# village_control.net
KiCad netlist of a schematic drawn in EAGLE
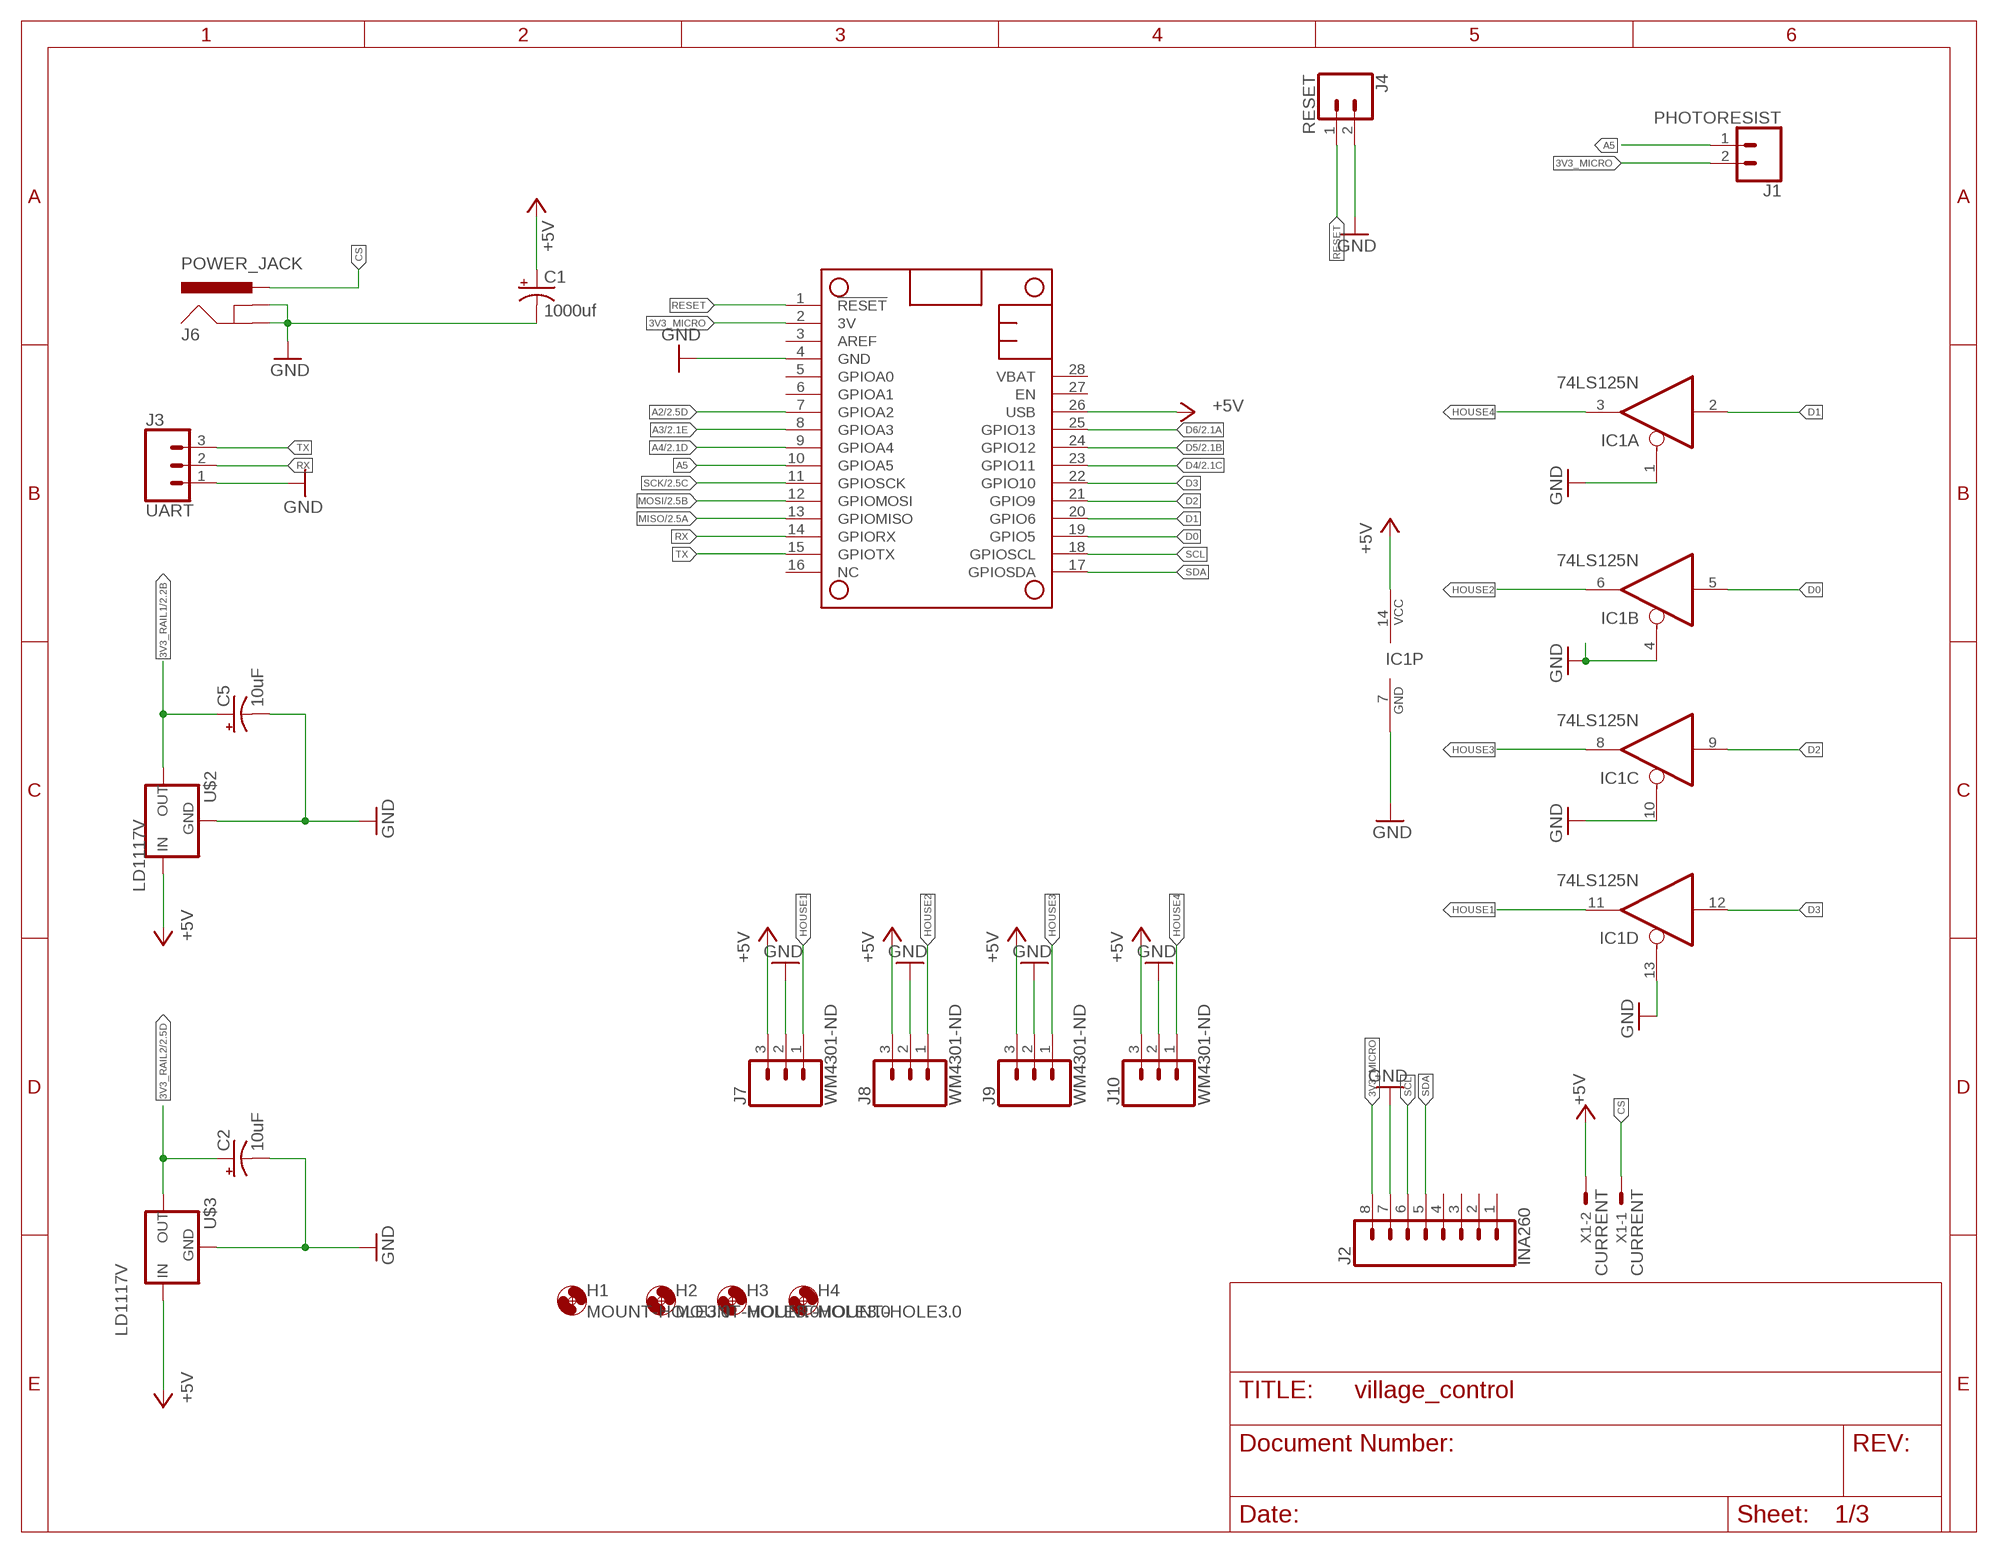
[diagram p0: schematic, sheet 1]
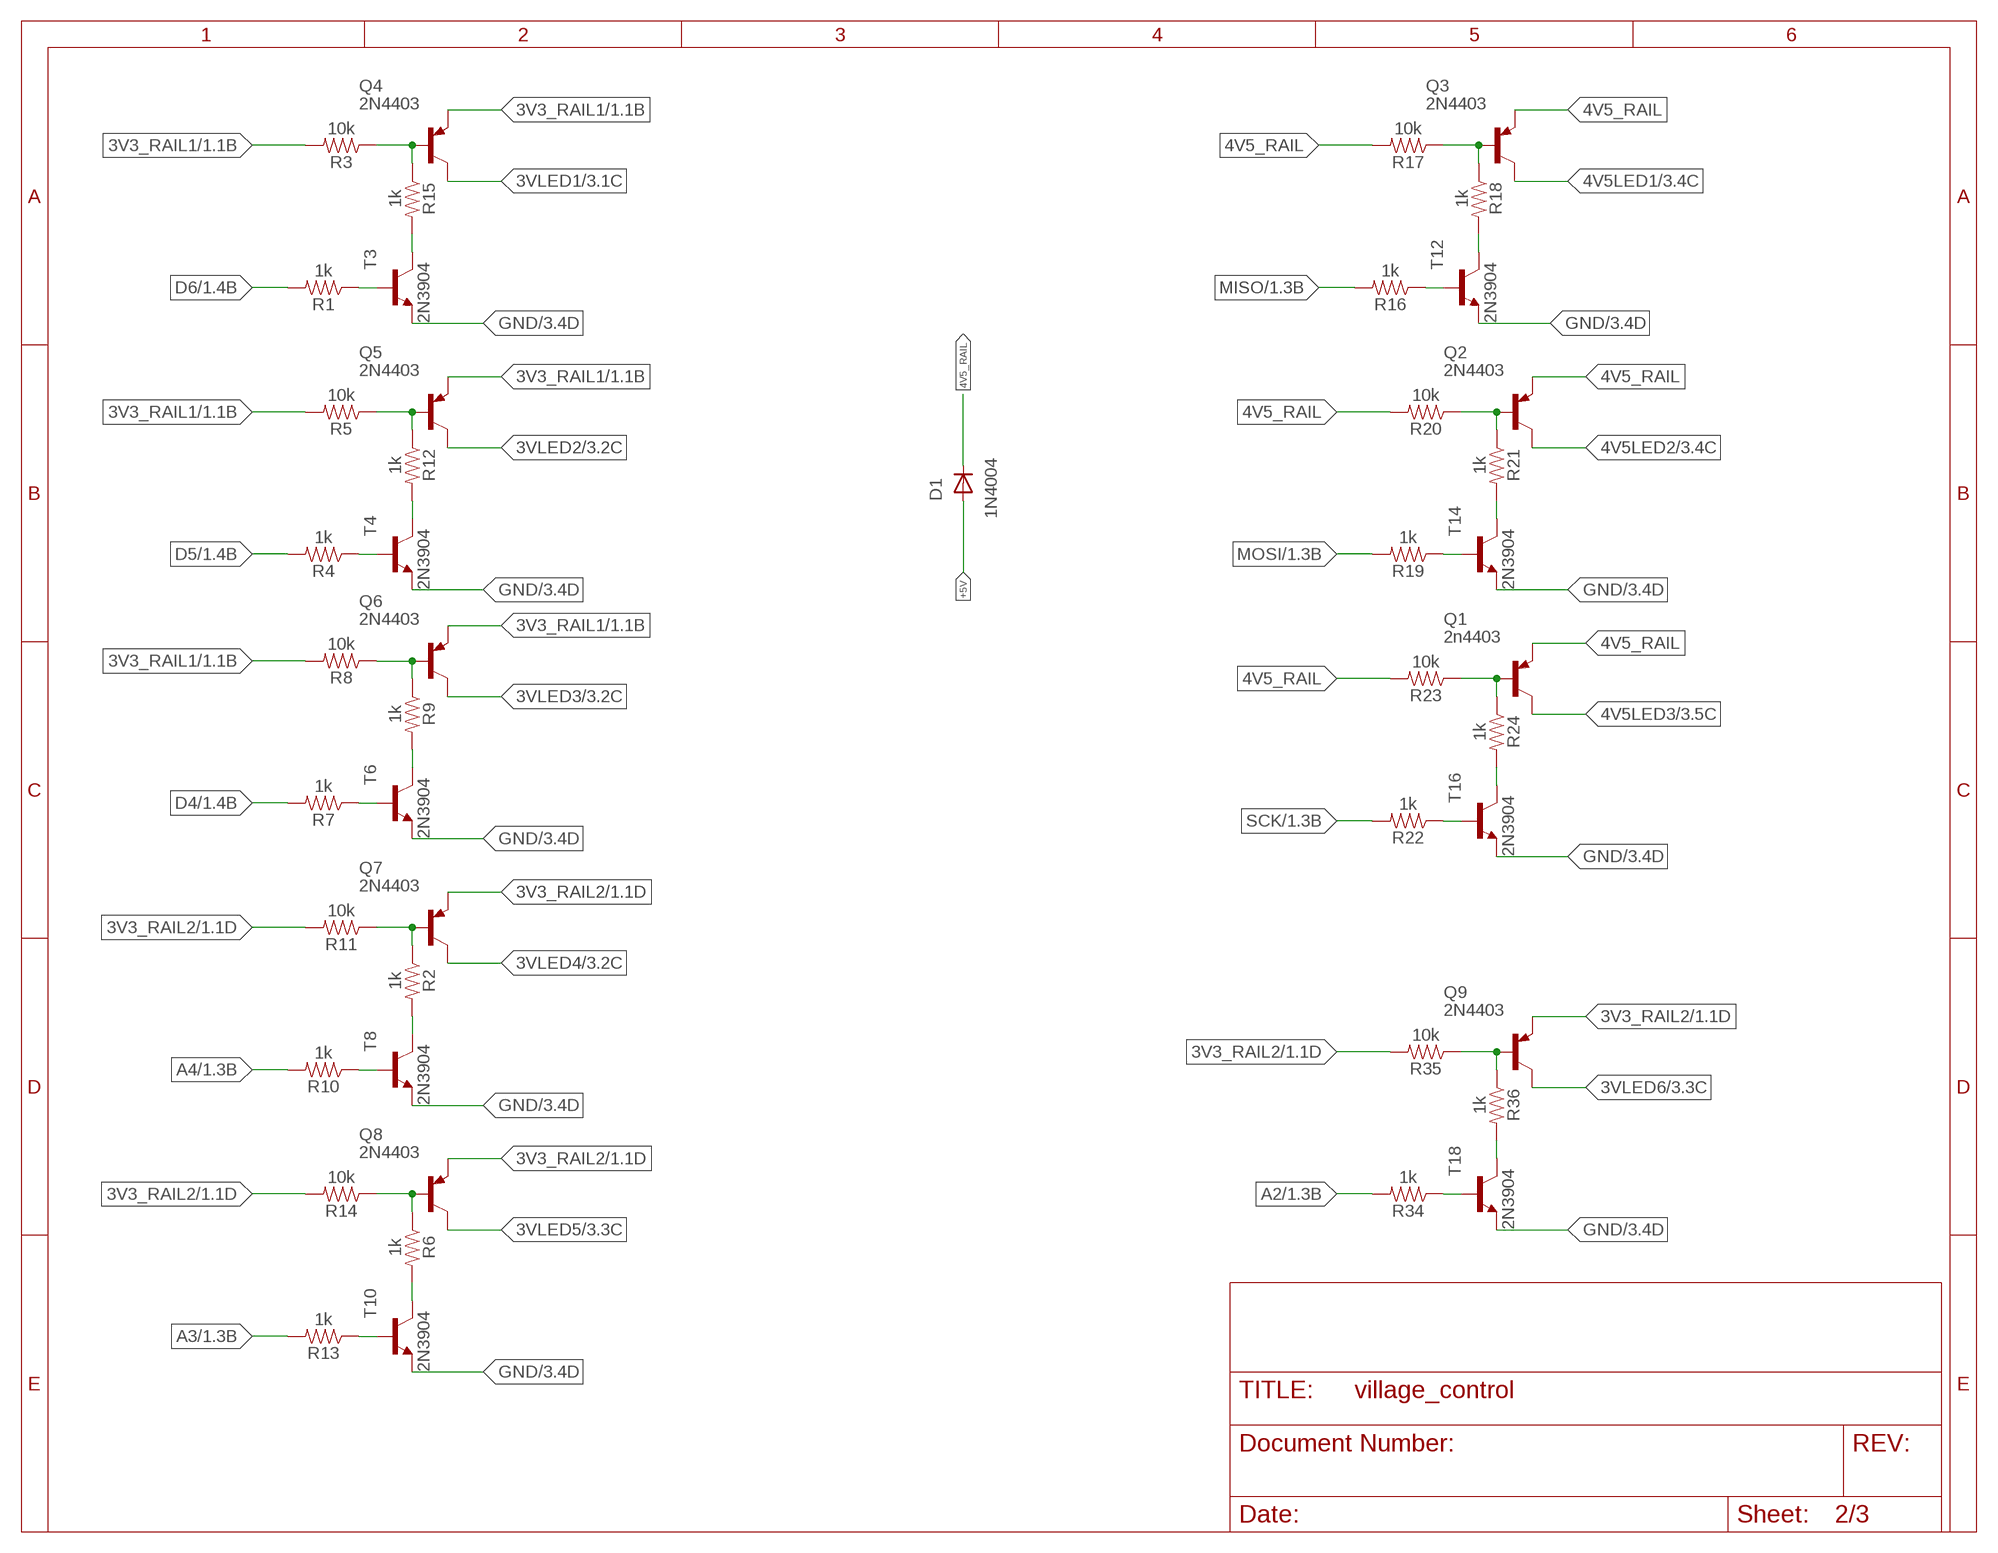
[diagram p1: schematic, sheet 2]
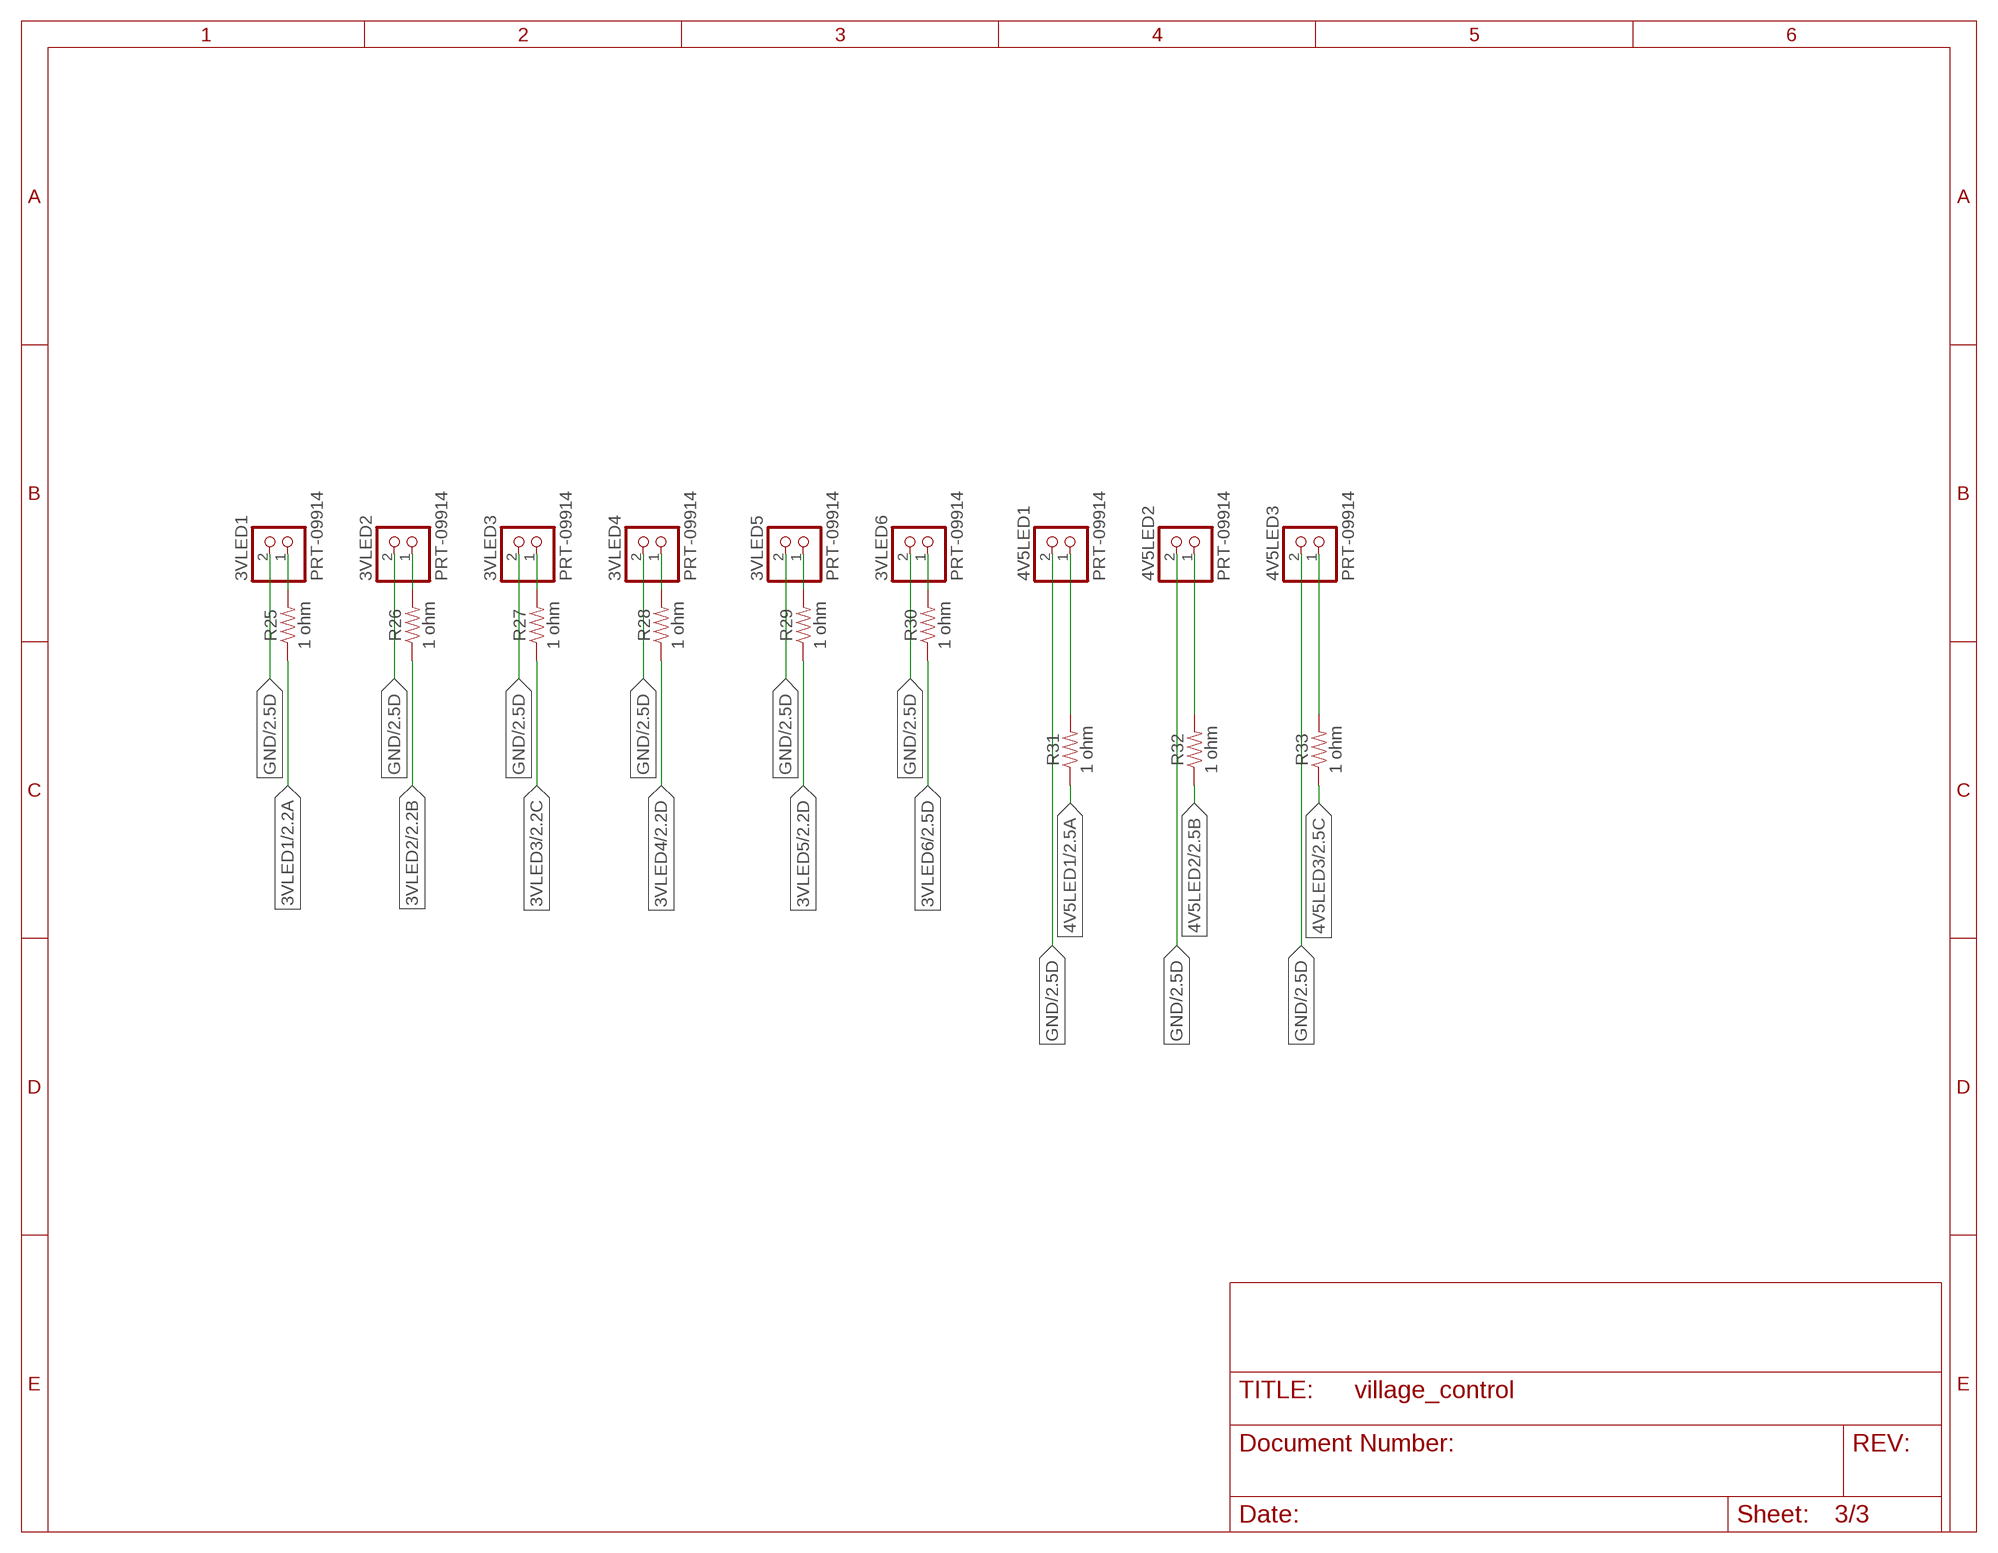
[diagram p2: schematic, sheet 3]

(export (version "E")
  (design (tool "Eeschema 10.0.6"))
  (components
    (comp (ref "D1")
      (value "1N4004")
      (footprint "eagle-import:DO41-10")
      (libsource (lib "eagle-import") (part "1N4004"))
    )
    (comp (ref "Q1")
      (value "2n4403")
      (footprint "eagle-import:TO92")
      (libsource (lib "eagle-import") (part "2N3906"))
    )
    (comp (ref "Q2")
      (value "2N4403")
      (footprint "eagle-import:TO92")
      (libsource (lib "eagle-import") (part "2N3906"))
    )
    (comp (ref "Q3")
      (value "2N4403")
      (footprint "eagle-import:TO92")
      (libsource (lib "eagle-import") (part "2N3906"))
    )
    (comp (ref "Q4")
      (value "2N4403")
      (footprint "eagle-import:TO92")
      (libsource (lib "eagle-import") (part "2N3906"))
    )
    (comp (ref "Q5")
      (value "2N4403")
      (footprint "eagle-import:TO92")
      (libsource (lib "eagle-import") (part "2N3906"))
    )
    (comp (ref "Q6")
      (value "2N4403")
      (footprint "eagle-import:TO92")
      (libsource (lib "eagle-import") (part "2N3906"))
    )
    (comp (ref "Q7")
      (value "2N4403")
      (footprint "eagle-import:TO92")
      (libsource (lib "eagle-import") (part "2N3906"))
    )
    (comp (ref "Q8")
      (value "2N4403")
      (footprint "eagle-import:TO92")
      (libsource (lib "eagle-import") (part "2N3906"))
    )
    (comp (ref "Q9")
      (value "2N4403")
      (footprint "eagle-import:TO92")
      (libsource (lib "eagle-import") (part "2N3906"))
    )
    (comp (ref "R1")
      (value "1k")
      (footprint "eagle-import:AXIAL-0.3")
      (libsource (lib "eagle-import") (part "1KOHM-HORIZ-1/4W-1%"))
    )
    (comp (ref "R2")
      (value "1k")
      (footprint "eagle-import:AXIAL-0.3")
      (libsource (lib "eagle-import") (part "1KOHM-HORIZ-1/4W-1%"))
    )
    (comp (ref "R3")
      (value "10k")
      (footprint "eagle-import:AXIAL-0.3")
      (libsource (lib "eagle-import") (part "1KOHM-HORIZ-1/4W-5%"))
    )
    (comp (ref "R4")
      (value "1k")
      (footprint "eagle-import:AXIAL-0.3")
      (libsource (lib "eagle-import") (part "1KOHM-HORIZ-1/4W-1%"))
    )
    (comp (ref "R5")
      (value "10k")
      (footprint "eagle-import:AXIAL-0.3")
      (libsource (lib "eagle-import") (part "1KOHM-HORIZ-1/4W-5%"))
    )
    (comp (ref "R6")
      (value "1k")
      (footprint "eagle-import:AXIAL-0.3")
      (libsource (lib "eagle-import") (part "1KOHM-HORIZ-1/4W-1%"))
    )
    (comp (ref "R7")
      (value "1k")
      (footprint "eagle-import:AXIAL-0.3")
      (libsource (lib "eagle-import") (part "1KOHM-HORIZ-1/4W-1%"))
    )
    (comp (ref "R8")
      (value "10k")
      (footprint "eagle-import:AXIAL-0.3")
      (libsource (lib "eagle-import") (part "1KOHM-HORIZ-1/4W-5%"))
    )
    (comp (ref "R9")
      (value "1k")
      (footprint "eagle-import:AXIAL-0.3")
      (libsource (lib "eagle-import") (part "1KOHM-HORIZ-1/4W-1%"))
    )
    (comp (ref "R10")
      (value "1k")
      (footprint "eagle-import:AXIAL-0.3")
      (libsource (lib "eagle-import") (part "1KOHM-HORIZ-1/4W-1%"))
    )
    (comp (ref "R11")
      (value "10k")
      (footprint "eagle-import:AXIAL-0.3")
      (libsource (lib "eagle-import") (part "1KOHM-HORIZ-1/4W-5%"))
    )
    (comp (ref "R12")
      (value "1k")
      (footprint "eagle-import:AXIAL-0.3")
      (libsource (lib "eagle-import") (part "1KOHM-HORIZ-1/4W-1%"))
    )
    (comp (ref "R13")
      (value "1k")
      (footprint "eagle-import:AXIAL-0.3")
      (libsource (lib "eagle-import") (part "1KOHM-HORIZ-1/4W-1%"))
    )
    (comp (ref "R14")
      (value "10k")
      (footprint "eagle-import:AXIAL-0.3")
      (libsource (lib "eagle-import") (part "1KOHM-HORIZ-1/4W-5%"))
    )
    (comp (ref "R15")
      (value "1k")
      (footprint "eagle-import:AXIAL-0.3")
      (libsource (lib "eagle-import") (part "1KOHM-HORIZ-1/4W-1%"))
    )
    (comp (ref "R16")
      (value "1k")
      (footprint "eagle-import:AXIAL-0.3")
      (libsource (lib "eagle-import") (part "1KOHM-HORIZ-1/4W-1%"))
    )
    (comp (ref "R17")
      (value "10k")
      (footprint "eagle-import:AXIAL-0.3")
      (libsource (lib "eagle-import") (part "1KOHM-HORIZ-1/4W-5%"))
    )
    (comp (ref "R18")
      (value "1k")
      (footprint "eagle-import:AXIAL-0.3")
      (libsource (lib "eagle-import") (part "1KOHM-HORIZ-1/4W-1%"))
    )
    (comp (ref "R19")
      (value "1k")
      (footprint "eagle-import:AXIAL-0.3")
      (libsource (lib "eagle-import") (part "1KOHM-HORIZ-1/4W-1%"))
    )
    (comp (ref "R20")
      (value "10k")
      (footprint "eagle-import:AXIAL-0.3")
      (libsource (lib "eagle-import") (part "1KOHM-HORIZ-1/4W-5%"))
    )
    (comp (ref "R21")
      (value "1k")
      (footprint "eagle-import:AXIAL-0.3")
      (libsource (lib "eagle-import") (part "1KOHM-HORIZ-1/4W-1%"))
    )
    (comp (ref "R22")
      (value "1k")
      (footprint "eagle-import:AXIAL-0.3")
      (libsource (lib "eagle-import") (part "1KOHM-HORIZ-1/4W-1%"))
    )
    (comp (ref "R23")
      (value "10k")
      (footprint "eagle-import:AXIAL-0.3")
      (libsource (lib "eagle-import") (part "1KOHM-HORIZ-1/4W-5%"))
    )
    (comp (ref "R24")
      (value "1k")
      (footprint "eagle-import:AXIAL-0.3")
      (libsource (lib "eagle-import") (part "1KOHM-HORIZ-1/4W-1%"))
    )
    (comp (ref "R34")
      (value "1k")
      (footprint "eagle-import:AXIAL-0.3")
      (libsource (lib "eagle-import") (part "1KOHM-HORIZ-1/4W-1%"))
    )
    (comp (ref "R35")
      (value "10k")
      (footprint "eagle-import:AXIAL-0.3")
      (libsource (lib "eagle-import") (part "1KOHM-HORIZ-1/4W-5%"))
    )
    (comp (ref "R36")
      (value "1k")
      (footprint "eagle-import:AXIAL-0.3")
      (libsource (lib "eagle-import") (part "1KOHM-HORIZ-1/4W-1%"))
    )
    (comp (ref "T3")
      (value "2N3904")
      (footprint "eagle-import:TO92")
      (libsource (lib "eagle-import") (part "2N3904"))
    )
    (comp (ref "T4")
      (value "2N3904")
      (footprint "eagle-import:TO92")
      (libsource (lib "eagle-import") (part "2N3904"))
    )
    (comp (ref "T6")
      (value "2N3904")
      (footprint "eagle-import:TO92")
      (libsource (lib "eagle-import") (part "2N3904"))
    )
    (comp (ref "T8")
      (value "2N3904")
      (footprint "eagle-import:TO92")
      (libsource (lib "eagle-import") (part "2N3904"))
    )
    (comp (ref "T10")
      (value "2N3904")
      (footprint "eagle-import:TO92")
      (libsource (lib "eagle-import") (part "2N3904"))
    )
    (comp (ref "T12")
      (value "2N3904")
      (footprint "eagle-import:TO92")
      (libsource (lib "eagle-import") (part "2N3904"))
    )
    (comp (ref "T14")
      (value "2N3904")
      (footprint "eagle-import:TO92")
      (libsource (lib "eagle-import") (part "2N3904"))
    )
    (comp (ref "T16")
      (value "2N3904")
      (footprint "eagle-import:TO92")
      (libsource (lib "eagle-import") (part "2N3904"))
    )
    (comp (ref "T18")
      (value "2N3904")
      (footprint "eagle-import:TO92")
      (libsource (lib "eagle-import") (part "2N3904"))
    )
    (comp (ref "3VLED1")
      (value "PRT-09914")
      (footprint "eagle-import:JST-PH-2-THM")
      (libsource (lib "eagle-import") (part "JST_2PIN-THM"))
    )
    (comp (ref "3VLED2")
      (value "PRT-09914")
      (footprint "eagle-import:JST-PH-2-THM")
      (libsource (lib "eagle-import") (part "JST_2PIN-THM"))
    )
    (comp (ref "3VLED3")
      (value "PRT-09914")
      (footprint "eagle-import:JST-PH-2-THM")
      (libsource (lib "eagle-import") (part "JST_2PIN-THM"))
    )
    (comp (ref "3VLED4")
      (value "PRT-09914")
      (footprint "eagle-import:JST-PH-2-THM")
      (libsource (lib "eagle-import") (part "JST_2PIN-THM"))
    )
    (comp (ref "3VLED5")
      (value "PRT-09914")
      (footprint "eagle-import:JST-PH-2-THM")
      (libsource (lib "eagle-import") (part "JST_2PIN-THM"))
    )
    (comp (ref "3VLED6")
      (value "PRT-09914")
      (footprint "eagle-import:JST-PH-2-THM")
      (libsource (lib "eagle-import") (part "JST_2PIN-THM"))
    )
    (comp (ref "4V5LED1")
      (value "PRT-09914")
      (footprint "eagle-import:JST-PH-2-THM")
      (libsource (lib "eagle-import") (part "JST_2PIN-THM"))
    )
    (comp (ref "4V5LED2")
      (value "PRT-09914")
      (footprint "eagle-import:JST-PH-2-THM")
      (libsource (lib "eagle-import") (part "JST_2PIN-THM"))
    )
    (comp (ref "4V5LED3")
      (value "PRT-09914")
      (footprint "eagle-import:JST-PH-2-THM")
      (libsource (lib "eagle-import") (part "JST_2PIN-THM"))
    )
    (comp (ref "R25")
      (value "1 ohm")
      (footprint "eagle-import:AXIAL-0.3")
      (libsource (lib "eagle-import") (part "1KOHM-HORIZ-1/4W-5%"))
    )
    (comp (ref "R26")
      (value "1 ohm")
      (footprint "eagle-import:AXIAL-0.3")
      (libsource (lib "eagle-import") (part "1KOHM-HORIZ-1/4W-5%"))
    )
    (comp (ref "R27")
      (value "1 ohm")
      (footprint "eagle-import:AXIAL-0.3")
      (libsource (lib "eagle-import") (part "1KOHM-HORIZ-1/4W-5%"))
    )
    (comp (ref "R28")
      (value "1 ohm")
      (footprint "eagle-import:AXIAL-0.3")
      (libsource (lib "eagle-import") (part "1KOHM-HORIZ-1/4W-5%"))
    )
    (comp (ref "R29")
      (value "1 ohm")
      (footprint "eagle-import:AXIAL-0.3")
      (libsource (lib "eagle-import") (part "1KOHM-HORIZ-1/4W-5%"))
    )
    (comp (ref "R30")
      (value "1 ohm")
      (footprint "eagle-import:AXIAL-0.3")
      (libsource (lib "eagle-import") (part "1KOHM-HORIZ-1/4W-5%"))
    )
    (comp (ref "R31")
      (value "1 ohm")
      (footprint "eagle-import:AXIAL-0.3")
      (libsource (lib "eagle-import") (part "1KOHM-HORIZ-1/4W-5%"))
    )
    (comp (ref "R32")
      (value "1 ohm")
      (footprint "eagle-import:AXIAL-0.3")
      (libsource (lib "eagle-import") (part "1KOHM-HORIZ-1/4W-5%"))
    )
    (comp (ref "R33")
      (value "1 ohm")
      (footprint "eagle-import:AXIAL-0.3")
      (libsource (lib "eagle-import") (part "1KOHM-HORIZ-1/4W-5%"))
    )
    (comp (ref "C1")
      (value "1000uf")
      (footprint "eagle-import:CPOL-RADIAL-5MM-10MM")
      (libsource (lib "eagle-import") (part "1000UF-RADIAL-5MM-25V-20%"))
    )
    (comp (ref "C2")
      (value "10uF")
      (footprint "eagle-import:CPOL-RADIAL-2.5MM-5MM-KIT")
      (libsource (lib "eagle-import") (part "10UF-POLAR-RADIAL-2.5MM-KIT-25V-20%"))
    )
    (comp (ref "C5")
      (value "10uF")
      (footprint "eagle-import:CPOL-RADIAL-2.5MM-5MM-KIT")
      (libsource (lib "eagle-import") (part "10UF-POLAR-RADIAL-2.5MM-KIT-25V-20%"))
    )
    (comp (ref "H1")
      (value "MOUNT-HOLE3.0")
      (footprint "eagle-import:3,0")
      (libsource (lib "eagle-import") (part "MOUNT-HOLE3.0"))
    )
    (comp (ref "H2")
      (value "MOUNT-HOLE3.0")
      (footprint "eagle-import:3,0")
      (libsource (lib "eagle-import") (part "MOUNT-HOLE3.0"))
    )
    (comp (ref "H3")
      (value "MOUNT-HOLE3.0")
      (footprint "eagle-import:3,0")
      (libsource (lib "eagle-import") (part "MOUNT-HOLE3.0"))
    )
    (comp (ref "H4")
      (value "MOUNT-HOLE3.0")
      (footprint "eagle-import:3,0")
      (libsource (lib "eagle-import") (part "MOUNT-HOLE3.0"))
    )
    (comp (ref "IC1")
      (value "74LS125N")
      (footprint "eagle-import:DIL14")
      (libsource (lib "eagle-import") (part "74125NLS"))
    )
    (comp (ref "J1")
      (value "PHOTORESIST")
      (footprint "eagle-import:1X02")
      (libsource (lib "eagle-import") (part "CONN_02"))
    )
    (comp (ref "J2")
      (value "INA260")
      (footprint "eagle-import:1X08")
      (libsource (lib "eagle-import") (part "CONN_08{dblquote}"))
    )
    (comp (ref "J3")
      (value "UART")
      (footprint "eagle-import:1X03")
      (libsource (lib "eagle-import") (part "CONN_03"))
    )
    (comp (ref "J4")
      (value "RESET")
      (footprint "eagle-import:1X02")
      (libsource (lib "eagle-import") (part "CONN_02"))
    )
    (comp (ref "J6")
      (value "POWER_JACK")
      (footprint "eagle-import:POWER_JACK_PTH")
      (libsource (lib "eagle-import") (part "POWER_JACK"))
    )
    (comp (ref "J7")
      (value "WM4301-ND")
      (footprint "eagle-import:1X03")
      (libsource (lib "eagle-import") (part "CONN_03"))
    )
    (comp (ref "J8")
      (value "WM4301-ND")
      (footprint "eagle-import:1X03")
      (libsource (lib "eagle-import") (part "CONN_03"))
    )
    (comp (ref "J9")
      (value "WM4301-ND")
      (footprint "eagle-import:1X03")
      (libsource (lib "eagle-import") (part "CONN_03"))
    )
    (comp (ref "J10")
      (value "WM4301-ND")
      (footprint "eagle-import:1X03")
      (libsource (lib "eagle-import") (part "CONN_03"))
    )
    (comp (ref "MS2")
      (value "FEATHERWING_NODIM")
      (footprint "eagle-import:FEATHERWING_DIM")
      (libsource (lib "eagle-import") (part "FEATHERWING_NODIM"))
    )
    (comp (ref "U$2")
      (value "LD1117V")
      (footprint "eagle-import:78XXL")
      (libsource (lib "eagle-import") (part "V_REG_LD1117VXX"))
    )
    (comp (ref "U$3")
      (value "LD1117V")
      (footprint "eagle-import:78XXL")
      (libsource (lib "eagle-import") (part "V_REG_LD1117VXX"))
    )
    (comp (ref "X1")
      (value "CURRENT")
      (footprint "eagle-import:KK-156-2")
      (fields (field (name "MF") "MOLEX"))
      (libsource (lib "eagle-import") (part "KK-156-2"))
    )
  )
  (nets
    (net (code "1") (name "+5V") (class "Default")
      (node (ref "C1") (pin "+") (pinfunction "+_+") (pintype "passive"))
      (node (ref "D1") (pin "A") (pinfunction "A_A") (pintype "passive"))
      (node (ref "IC1") (pin "14") (pinfunction "VCC_14") (pintype "power_in"))
      (node (ref "J10") (pin "3") (pinfunction "3_3") (pintype "passive"))
      (node (ref "J7") (pin "3") (pinfunction "3_3") (pintype "passive"))
      (node (ref "J8") (pin "3") (pinfunction "3_3") (pintype "passive"))
      (node (ref "J9") (pin "3") (pinfunction "3_3") (pintype "passive"))
      (node (ref "MS2") (pin "26") (pinfunction "USB_26") (pintype "power_in"))
      (node (ref "U$2") (pin "OUT") (pinfunction "IN_OUT") (pintype "input"))
      (node (ref "U$3") (pin "OUT") (pinfunction "IN_OUT") (pintype "input"))
      (node (ref "X1") (pin "2") (pinfunction "S_2") (pintype "passive"))
    )
    (net (code "2") (name "3V3_MICRO") (class "Default")
      (node (ref "J1") (pin "2") (pinfunction "2_2") (pintype "passive"))
      (node (ref "J2") (pin "8") (pinfunction "8_8") (pintype "passive"))
      (node (ref "MS2") (pin "2") (pinfunction "3V_2") (pintype "power_in"))
    )
    (net (code "3") (name "3V3_RAIL1") (class "Default")
      (node (ref "C5") (pin "1") (pinfunction "+_1") (pintype "passive"))
      (node (ref "Q4") (pin "3") (pinfunction "E_3") (pintype "passive"))
      (node (ref "Q5") (pin "3") (pinfunction "E_3") (pintype "passive"))
      (node (ref "Q6") (pin "3") (pinfunction "E_3") (pintype "passive"))
      (node (ref "R3") (pin "P$2") (pinfunction "2_P$2") (pintype "passive"))
      (node (ref "R5") (pin "P$2") (pinfunction "2_P$2") (pintype "passive"))
      (node (ref "R8") (pin "P$2") (pinfunction "2_P$2") (pintype "passive"))
      (node (ref "U$2") (pin "GND") (pinfunction "OUT_GND") (pintype "passive"))
    )
    (net (code "4") (name "3V3_RAIL2") (class "Default")
      (node (ref "C2") (pin "1") (pinfunction "+_1") (pintype "passive"))
      (node (ref "Q7") (pin "3") (pinfunction "E_3") (pintype "passive"))
      (node (ref "Q8") (pin "3") (pinfunction "E_3") (pintype "passive"))
      (node (ref "Q9") (pin "3") (pinfunction "E_3") (pintype "passive"))
      (node (ref "R11") (pin "P$2") (pinfunction "2_P$2") (pintype "passive"))
      (node (ref "R14") (pin "P$2") (pinfunction "2_P$2") (pintype "passive"))
      (node (ref "R35") (pin "P$2") (pinfunction "2_P$2") (pintype "passive"))
      (node (ref "U$3") (pin "GND") (pinfunction "OUT_GND") (pintype "passive"))
    )
    (net (code "5") (name "3VLED1") (class "Default")
      (node (ref "Q4") (pin "1") (pinfunction "C_1") (pintype "passive"))
      (node (ref "R25") (pin "P$1") (pinfunction "1_P$1") (pintype "passive"))
    )
    (net (code "6") (name "3VLED2") (class "Default")
      (node (ref "Q5") (pin "1") (pinfunction "C_1") (pintype "passive"))
      (node (ref "R26") (pin "P$1") (pinfunction "1_P$1") (pintype "passive"))
    )
    (net (code "7") (name "3VLED3") (class "Default")
      (node (ref "Q6") (pin "1") (pinfunction "C_1") (pintype "passive"))
      (node (ref "R27") (pin "P$1") (pinfunction "1_P$1") (pintype "passive"))
    )
    (net (code "8") (name "3VLED4") (class "Default")
      (node (ref "Q7") (pin "1") (pinfunction "C_1") (pintype "passive"))
      (node (ref "R28") (pin "P$1") (pinfunction "1_P$1") (pintype "passive"))
    )
    (net (code "9") (name "3VLED5") (class "Default")
      (node (ref "Q8") (pin "1") (pinfunction "C_1") (pintype "passive"))
      (node (ref "R29") (pin "P$1") (pinfunction "1_P$1") (pintype "passive"))
    )
    (net (code "10") (name "3VLED6") (class "Default")
      (node (ref "Q9") (pin "1") (pinfunction "C_1") (pintype "passive"))
      (node (ref "R30") (pin "P$1") (pinfunction "1_P$1") (pintype "passive"))
    )
    (net (code "11") (name "4V5LED1") (class "Default")
      (node (ref "Q3") (pin "1") (pinfunction "C_1") (pintype "passive"))
      (node (ref "R31") (pin "P$1") (pinfunction "1_P$1") (pintype "passive"))
    )
    (net (code "12") (name "4V5LED2") (class "Default")
      (node (ref "Q2") (pin "1") (pinfunction "C_1") (pintype "passive"))
      (node (ref "R32") (pin "P$1") (pinfunction "1_P$1") (pintype "passive"))
    )
    (net (code "13") (name "4V5LED3") (class "Default")
      (node (ref "Q1") (pin "1") (pinfunction "C_1") (pintype "passive"))
      (node (ref "R33") (pin "P$1") (pinfunction "1_P$1") (pintype "passive"))
    )
    (net (code "14") (name "4V5_RAIL") (class "Default")
      (node (ref "D1") (pin "C") (pinfunction "C_C") (pintype "passive"))
      (node (ref "Q1") (pin "3") (pinfunction "E_3") (pintype "passive"))
      (node (ref "Q2") (pin "3") (pinfunction "E_3") (pintype "passive"))
      (node (ref "Q3") (pin "3") (pinfunction "E_3") (pintype "passive"))
      (node (ref "R17") (pin "P$2") (pinfunction "2_P$2") (pintype "passive"))
      (node (ref "R20") (pin "P$2") (pinfunction "2_P$2") (pintype "passive"))
      (node (ref "R23") (pin "P$2") (pinfunction "2_P$2") (pintype "passive"))
    )
    (net (code "15") (name "A2") (class "Default")
      (node (ref "MS2") (pin "7") (pinfunction "GPIOA2_7") (pintype "bidirectional"))
      (node (ref "R34") (pin "P$2") (pinfunction "2_P$2") (pintype "passive"))
    )
    (net (code "16") (name "A3") (class "Default")
      (node (ref "MS2") (pin "8") (pinfunction "GPIOA3_8") (pintype "bidirectional"))
      (node (ref "R13") (pin "P$2") (pinfunction "2_P$2") (pintype "passive"))
    )
    (net (code "17") (name "A4") (class "Default")
      (node (ref "MS2") (pin "9") (pinfunction "GPIOA4_9") (pintype "bidirectional"))
      (node (ref "R10") (pin "P$2") (pinfunction "2_P$2") (pintype "passive"))
    )
    (net (code "18") (name "A5") (class "Default")
      (node (ref "J1") (pin "1") (pinfunction "1_1") (pintype "passive"))
      (node (ref "MS2") (pin "10") (pinfunction "GPIOA5_10") (pintype "bidirectional"))
    )
    (net (code "19") (name "CS") (class "Default")
      (node (ref "J6") (pin "PWR") (pinfunction "PWR_PWR") (pintype "bidirectional"))
      (node (ref "X1") (pin "1") (pinfunction "S_1") (pintype "passive"))
    )
    (net (code "20") (name "D0") (class "Default")
      (node (ref "IC1") (pin "5") (pinfunction "I_5") (pintype "input"))
      (node (ref "MS2") (pin "19") (pinfunction "GPIO5_19") (pintype "bidirectional"))
    )
    (net (code "21") (name "D1") (class "Default")
      (node (ref "IC1") (pin "2") (pinfunction "I_2") (pintype "input"))
      (node (ref "MS2") (pin "20") (pinfunction "GPIO6_20") (pintype "bidirectional"))
    )
    (net (code "22") (name "D2") (class "Default")
      (node (ref "IC1") (pin "9") (pinfunction "I_9") (pintype "input"))
      (node (ref "MS2") (pin "21") (pinfunction "GPIO9_21") (pintype "bidirectional"))
    )
    (net (code "23") (name "D3") (class "Default")
      (node (ref "IC1") (pin "12") (pinfunction "I_12") (pintype "input"))
      (node (ref "MS2") (pin "22") (pinfunction "GPIO10_22") (pintype "bidirectional"))
    )
    (net (code "24") (name "D4") (class "Default")
      (node (ref "MS2") (pin "23") (pinfunction "GPIO11_23") (pintype "bidirectional"))
      (node (ref "R7") (pin "P$2") (pinfunction "2_P$2") (pintype "passive"))
    )
    (net (code "25") (name "D5") (class "Default")
      (node (ref "MS2") (pin "24") (pinfunction "GPIO12_24") (pintype "bidirectional"))
      (node (ref "R4") (pin "P$2") (pinfunction "2_P$2") (pintype "passive"))
    )
    (net (code "26") (name "D6") (class "Default")
      (node (ref "MS2") (pin "25") (pinfunction "GPIO13_25") (pintype "bidirectional"))
      (node (ref "R1") (pin "P$2") (pinfunction "2_P$2") (pintype "passive"))
    )
    (net (code "27") (name "GND") (class "Default")
      (node (ref "3VLED1") (pin "2") (pinfunction "1_2") (pintype "passive"))
      (node (ref "3VLED2") (pin "2") (pinfunction "1_2") (pintype "passive"))
      (node (ref "3VLED3") (pin "2") (pinfunction "1_2") (pintype "passive"))
      (node (ref "3VLED4") (pin "2") (pinfunction "1_2") (pintype "passive"))
      (node (ref "3VLED5") (pin "2") (pinfunction "1_2") (pintype "passive"))
      (node (ref "3VLED6") (pin "2") (pinfunction "1_2") (pintype "passive"))
      (node (ref "4V5LED1") (pin "2") (pinfunction "1_2") (pintype "passive"))
      (node (ref "4V5LED2") (pin "2") (pinfunction "1_2") (pintype "passive"))
      (node (ref "4V5LED3") (pin "2") (pinfunction "1_2") (pintype "passive"))
      (node (ref "C1") (pin "-") (pinfunction "-_-") (pintype "passive"))
      (node (ref "C2") (pin "2") (pinfunction "-_2") (pintype "passive"))
      (node (ref "C5") (pin "2") (pinfunction "-_2") (pintype "passive"))
      (node (ref "IC1") (pin "1") (pinfunction "OE_1") (pintype "input"))
      (node (ref "IC1") (pin "10") (pinfunction "OE_10") (pintype "input"))
      (node (ref "IC1") (pin "13") (pinfunction "OE_13") (pintype "input"))
      (node (ref "IC1") (pin "4") (pinfunction "OE_4") (pintype "input"))
      (node (ref "IC1") (pin "7") (pinfunction "GND_7") (pintype "power_in"))
      (node (ref "J10") (pin "2") (pinfunction "2_2") (pintype "passive"))
      (node (ref "J2") (pin "7") (pinfunction "7_7") (pintype "passive"))
      (node (ref "J3") (pin "1") (pinfunction "1_1") (pintype "passive"))
      (node (ref "J4") (pin "2") (pinfunction "2_2") (pintype "passive"))
      (node (ref "J6") (pin "GND") (pinfunction "GND_GND") (pintype "bidirectional"))
      (node (ref "J6") (pin "GNDBREAK") (pinfunction "GNDBREAK_GNDBREAK") (pintype "bidirectional"))
      (node (ref "J7") (pin "2") (pinfunction "2_2") (pintype "passive"))
      (node (ref "J8") (pin "2") (pinfunction "2_2") (pintype "passive"))
      (node (ref "J9") (pin "2") (pinfunction "2_2") (pintype "passive"))
      (node (ref "MS2") (pin "4") (pinfunction "GND_4") (pintype "power_in"))
      (node (ref "T10") (pin "3") (pinfunction "E_3") (pintype "passive"))
      (node (ref "T12") (pin "3") (pinfunction "E_3") (pintype "passive"))
      (node (ref "T14") (pin "3") (pinfunction "E_3") (pintype "passive"))
      (node (ref "T16") (pin "3") (pinfunction "E_3") (pintype "passive"))
      (node (ref "T18") (pin "3") (pinfunction "E_3") (pintype "passive"))
      (node (ref "T3") (pin "3") (pinfunction "E_3") (pintype "passive"))
      (node (ref "T4") (pin "3") (pinfunction "E_3") (pintype "passive"))
      (node (ref "T6") (pin "3") (pinfunction "E_3") (pintype "passive"))
      (node (ref "T8") (pin "3") (pinfunction "E_3") (pintype "passive"))
      (node (ref "U$2") (pin "IN") (pinfunction "GND_IN") (pintype "input"))
      (node (ref "U$3") (pin "IN") (pinfunction "GND_IN") (pintype "input"))
    )
    (net (code "28") (name "HOUSE1") (class "Default")
      (node (ref "IC1") (pin "11") (pinfunction "O_11") (pintype "tri_state"))
      (node (ref "J7") (pin "1") (pinfunction "1_1") (pintype "passive"))
    )
    (net (code "29") (name "HOUSE2") (class "Default")
      (node (ref "IC1") (pin "6") (pinfunction "O_6") (pintype "tri_state"))
      (node (ref "J8") (pin "1") (pinfunction "1_1") (pintype "passive"))
    )
    (net (code "30") (name "HOUSE3") (class "Default")
      (node (ref "IC1") (pin "8") (pinfunction "O_8") (pintype "tri_state"))
      (node (ref "J9") (pin "1") (pinfunction "1_1") (pintype "passive"))
    )
    (net (code "31") (name "HOUSE4") (class "Default")
      (node (ref "IC1") (pin "3") (pinfunction "O_3") (pintype "tri_state"))
      (node (ref "J10") (pin "1") (pinfunction "1_1") (pintype "passive"))
    )
    (net (code "32") (name "MISO") (class "Default")
      (node (ref "MS2") (pin "13") (pinfunction "GPIOMISO_13") (pintype "bidirectional"))
      (node (ref "R16") (pin "P$2") (pinfunction "2_P$2") (pintype "passive"))
    )
    (net (code "33") (name "MOSI") (class "Default")
      (node (ref "MS2") (pin "12") (pinfunction "GPIOMOSI_12") (pintype "bidirectional"))
      (node (ref "R19") (pin "P$2") (pinfunction "2_P$2") (pintype "passive"))
    )
    (net (code "34") (name "Net-(3VLED1-2)") (class "Default")
      (node (ref "3VLED1") (pin "1") (pinfunction "2_1") (pintype "passive"))
      (node (ref "R25") (pin "P$2") (pinfunction "2_P$2") (pintype "passive"))
    )
    (net (code "35") (name "Net-(3VLED2-2)") (class "Default")
      (node (ref "3VLED2") (pin "1") (pinfunction "2_1") (pintype "passive"))
      (node (ref "R26") (pin "P$2") (pinfunction "2_P$2") (pintype "passive"))
    )
    (net (code "36") (name "Net-(3VLED3-2)") (class "Default")
      (node (ref "3VLED3") (pin "1") (pinfunction "2_1") (pintype "passive"))
      (node (ref "R27") (pin "P$2") (pinfunction "2_P$2") (pintype "passive"))
    )
    (net (code "37") (name "Net-(3VLED4-2)") (class "Default")
      (node (ref "3VLED4") (pin "1") (pinfunction "2_1") (pintype "passive"))
      (node (ref "R28") (pin "P$2") (pinfunction "2_P$2") (pintype "passive"))
    )
    (net (code "38") (name "Net-(3VLED5-2)") (class "Default")
      (node (ref "3VLED5") (pin "1") (pinfunction "2_1") (pintype "passive"))
      (node (ref "R29") (pin "P$2") (pinfunction "2_P$2") (pintype "passive"))
    )
    (net (code "39") (name "Net-(3VLED6-2)") (class "Default")
      (node (ref "3VLED6") (pin "1") (pinfunction "2_1") (pintype "passive"))
      (node (ref "R30") (pin "P$2") (pinfunction "2_P$2") (pintype "passive"))
    )
    (net (code "40") (name "Net-(4V5LED1-2)") (class "Default")
      (node (ref "4V5LED1") (pin "1") (pinfunction "2_1") (pintype "passive"))
      (node (ref "R31") (pin "P$2") (pinfunction "2_P$2") (pintype "passive"))
    )
    (net (code "41") (name "Net-(4V5LED2-2)") (class "Default")
      (node (ref "4V5LED2") (pin "1") (pinfunction "2_1") (pintype "passive"))
      (node (ref "R32") (pin "P$2") (pinfunction "2_P$2") (pintype "passive"))
    )
    (net (code "42") (name "Net-(4V5LED3-2)") (class "Default")
      (node (ref "4V5LED3") (pin "1") (pinfunction "2_1") (pintype "passive"))
      (node (ref "R33") (pin "P$2") (pinfunction "2_P$2") (pintype "passive"))
    )
    (net (code "43") (name "Net-(Q1-B)") (class "Default")
      (node (ref "Q1") (pin "2") (pinfunction "B_2") (pintype "passive"))
      (node (ref "R23") (pin "P$1") (pinfunction "1_P$1") (pintype "passive"))
      (node (ref "R24") (pin "P$1") (pinfunction "1_P$1") (pintype "passive"))
    )
    (net (code "44") (name "Net-(Q2-B)") (class "Default")
      (node (ref "Q2") (pin "2") (pinfunction "B_2") (pintype "passive"))
      (node (ref "R20") (pin "P$1") (pinfunction "1_P$1") (pintype "passive"))
      (node (ref "R21") (pin "P$1") (pinfunction "1_P$1") (pintype "passive"))
    )
    (net (code "45") (name "Net-(Q3-B)") (class "Default")
      (node (ref "Q3") (pin "2") (pinfunction "B_2") (pintype "passive"))
      (node (ref "R17") (pin "P$1") (pinfunction "1_P$1") (pintype "passive"))
      (node (ref "R18") (pin "P$1") (pinfunction "1_P$1") (pintype "passive"))
    )
    (net (code "46") (name "Net-(Q4-B)") (class "Default")
      (node (ref "Q4") (pin "2") (pinfunction "B_2") (pintype "passive"))
      (node (ref "R15") (pin "P$1") (pinfunction "1_P$1") (pintype "passive"))
      (node (ref "R3") (pin "P$1") (pinfunction "1_P$1") (pintype "passive"))
    )
    (net (code "47") (name "Net-(Q5-B)") (class "Default")
      (node (ref "Q5") (pin "2") (pinfunction "B_2") (pintype "passive"))
      (node (ref "R12") (pin "P$1") (pinfunction "1_P$1") (pintype "passive"))
      (node (ref "R5") (pin "P$1") (pinfunction "1_P$1") (pintype "passive"))
    )
    (net (code "48") (name "Net-(Q6-B)") (class "Default")
      (node (ref "Q6") (pin "2") (pinfunction "B_2") (pintype "passive"))
      (node (ref "R8") (pin "P$1") (pinfunction "1_P$1") (pintype "passive"))
      (node (ref "R9") (pin "P$1") (pinfunction "1_P$1") (pintype "passive"))
    )
    (net (code "49") (name "Net-(Q7-B)") (class "Default")
      (node (ref "Q7") (pin "2") (pinfunction "B_2") (pintype "passive"))
      (node (ref "R11") (pin "P$1") (pinfunction "1_P$1") (pintype "passive"))
      (node (ref "R2") (pin "P$1") (pinfunction "1_P$1") (pintype "passive"))
    )
    (net (code "50") (name "Net-(Q8-B)") (class "Default")
      (node (ref "Q8") (pin "2") (pinfunction "B_2") (pintype "passive"))
      (node (ref "R14") (pin "P$1") (pinfunction "1_P$1") (pintype "passive"))
      (node (ref "R6") (pin "P$1") (pinfunction "1_P$1") (pintype "passive"))
    )
    (net (code "51") (name "Net-(Q9-B)") (class "Default")
      (node (ref "Q9") (pin "2") (pinfunction "B_2") (pintype "passive"))
      (node (ref "R35") (pin "P$1") (pinfunction "1_P$1") (pintype "passive"))
      (node (ref "R36") (pin "P$1") (pinfunction "1_P$1") (pintype "passive"))
    )
    (net (code "52") (name "Net-(R1-1)") (class "Default")
      (node (ref "R1") (pin "P$1") (pinfunction "1_P$1") (pintype "passive"))
      (node (ref "T3") (pin "2") (pinfunction "B_2") (pintype "passive"))
    )
    (net (code "53") (name "Net-(R2-2)") (class "Default")
      (node (ref "R2") (pin "P$2") (pinfunction "2_P$2") (pintype "passive"))
      (node (ref "T8") (pin "1") (pinfunction "C_1") (pintype "passive"))
    )
    (net (code "54") (name "Net-(R4-1)") (class "Default")
      (node (ref "R4") (pin "P$1") (pinfunction "1_P$1") (pintype "passive"))
      (node (ref "T4") (pin "2") (pinfunction "B_2") (pintype "passive"))
    )
    (net (code "55") (name "Net-(R6-2)") (class "Default")
      (node (ref "R6") (pin "P$2") (pinfunction "2_P$2") (pintype "passive"))
      (node (ref "T10") (pin "1") (pinfunction "C_1") (pintype "passive"))
    )
    (net (code "56") (name "Net-(R7-1)") (class "Default")
      (node (ref "R7") (pin "P$1") (pinfunction "1_P$1") (pintype "passive"))
      (node (ref "T6") (pin "2") (pinfunction "B_2") (pintype "passive"))
    )
    (net (code "57") (name "Net-(R9-2)") (class "Default")
      (node (ref "R9") (pin "P$2") (pinfunction "2_P$2") (pintype "passive"))
      (node (ref "T6") (pin "1") (pinfunction "C_1") (pintype "passive"))
    )
    (net (code "58") (name "Net-(R10-1)") (class "Default")
      (node (ref "R10") (pin "P$1") (pinfunction "1_P$1") (pintype "passive"))
      (node (ref "T8") (pin "2") (pinfunction "B_2") (pintype "passive"))
    )
    (net (code "59") (name "Net-(R12-2)") (class "Default")
      (node (ref "R12") (pin "P$2") (pinfunction "2_P$2") (pintype "passive"))
      (node (ref "T4") (pin "1") (pinfunction "C_1") (pintype "passive"))
    )
    (net (code "60") (name "Net-(R13-1)") (class "Default")
      (node (ref "R13") (pin "P$1") (pinfunction "1_P$1") (pintype "passive"))
      (node (ref "T10") (pin "2") (pinfunction "B_2") (pintype "passive"))
    )
    (net (code "61") (name "Net-(R15-2)") (class "Default")
      (node (ref "R15") (pin "P$2") (pinfunction "2_P$2") (pintype "passive"))
      (node (ref "T3") (pin "1") (pinfunction "C_1") (pintype "passive"))
    )
    (net (code "62") (name "Net-(R16-1)") (class "Default")
      (node (ref "R16") (pin "P$1") (pinfunction "1_P$1") (pintype "passive"))
      (node (ref "T12") (pin "2") (pinfunction "B_2") (pintype "passive"))
    )
    (net (code "63") (name "Net-(R18-2)") (class "Default")
      (node (ref "R18") (pin "P$2") (pinfunction "2_P$2") (pintype "passive"))
      (node (ref "T12") (pin "1") (pinfunction "C_1") (pintype "passive"))
    )
    (net (code "64") (name "Net-(R19-1)") (class "Default")
      (node (ref "R19") (pin "P$1") (pinfunction "1_P$1") (pintype "passive"))
      (node (ref "T14") (pin "2") (pinfunction "B_2") (pintype "passive"))
    )
    (net (code "65") (name "Net-(R21-2)") (class "Default")
      (node (ref "R21") (pin "P$2") (pinfunction "2_P$2") (pintype "passive"))
      (node (ref "T14") (pin "1") (pinfunction "C_1") (pintype "passive"))
    )
    (net (code "66") (name "Net-(R22-1)") (class "Default")
      (node (ref "R22") (pin "P$1") (pinfunction "1_P$1") (pintype "passive"))
      (node (ref "T16") (pin "2") (pinfunction "B_2") (pintype "passive"))
    )
    (net (code "67") (name "Net-(R24-2)") (class "Default")
      (node (ref "R24") (pin "P$2") (pinfunction "2_P$2") (pintype "passive"))
      (node (ref "T16") (pin "1") (pinfunction "C_1") (pintype "passive"))
    )
    (net (code "68") (name "Net-(R34-1)") (class "Default")
      (node (ref "R34") (pin "P$1") (pinfunction "1_P$1") (pintype "passive"))
      (node (ref "T18") (pin "2") (pinfunction "B_2") (pintype "passive"))
    )
    (net (code "69") (name "Net-(R36-2)") (class "Default")
      (node (ref "R36") (pin "P$2") (pinfunction "2_P$2") (pintype "passive"))
      (node (ref "T18") (pin "1") (pinfunction "C_1") (pintype "passive"))
    )
    (net (code "70") (name "RESET") (class "Default")
      (node (ref "J4") (pin "1") (pinfunction "1_1") (pintype "passive"))
      (node (ref "MS2") (pin "1") (pinfunction "~{RESET}_1") (pintype "input"))
    )
    (net (code "71") (name "RX") (class "Default")
      (node (ref "J3") (pin "2") (pinfunction "2_2") (pintype "passive"))
      (node (ref "MS2") (pin "14") (pinfunction "GPIORX_14") (pintype "bidirectional"))
    )
    (net (code "72") (name "SCK") (class "Default")
      (node (ref "MS2") (pin "11") (pinfunction "GPIOSCK_11") (pintype "bidirectional"))
      (node (ref "R22") (pin "P$2") (pinfunction "2_P$2") (pintype "passive"))
    )
    (net (code "73") (name "SCL") (class "Default")
      (node (ref "J2") (pin "6") (pinfunction "6_6") (pintype "passive"))
      (node (ref "MS2") (pin "18") (pinfunction "GPIOSCL_18") (pintype "bidirectional"))
    )
    (net (code "74") (name "SDA") (class "Default")
      (node (ref "J2") (pin "5") (pinfunction "5_5") (pintype "passive"))
      (node (ref "MS2") (pin "17") (pinfunction "GPIOSDA_17") (pintype "bidirectional"))
    )
    (net (code "75") (name "TX") (class "Default")
      (node (ref "J3") (pin "3") (pinfunction "3_3") (pintype "passive"))
      (node (ref "MS2") (pin "15") (pinfunction "GPIOTX_15") (pintype "bidirectional"))
    )
    (net (code "76") (name "VBAT") (class "Default")
      (node (ref "MS2") (pin "28") (pinfunction "VBAT_28") (pintype "power_in"))
    )
    (net (code "77") (name "unconnected-(J2-Pad1)") (class "Default")
      (node (ref "J2") (pin "1") (pinfunction "1_1") (pintype "passive"))
    )
    (net (code "78") (name "unconnected-(J2-Pad2)") (class "Default")
      (node (ref "J2") (pin "2") (pinfunction "2_2") (pintype "passive"))
    )
    (net (code "79") (name "unconnected-(J2-Pad3)") (class "Default")
      (node (ref "J2") (pin "3") (pinfunction "3_3") (pintype "passive"))
    )
    (net (code "80") (name "unconnected-(J2-Pad4)") (class "Default")
      (node (ref "J2") (pin "4") (pinfunction "4_4") (pintype "passive"))
    )
    (net (code "81") (name "unconnected-(MS2-AREF-Pad3)") (class "Default")
      (node (ref "MS2") (pin "3") (pinfunction "AREF_3") (pintype "passive"))
    )
    (net (code "82") (name "unconnected-(MS2-EN-Pad27)") (class "Default")
      (node (ref "MS2") (pin "27") (pinfunction "EN_27") (pintype "passive"))
    )
    (net (code "83") (name "unconnected-(MS2-GPIOA0-Pad5)") (class "Default")
      (node (ref "MS2") (pin "5") (pinfunction "GPIOA0_5") (pintype "bidirectional"))
    )
    (net (code "84") (name "unconnected-(MS2-GPIOA1-Pad6)") (class "Default")
      (node (ref "MS2") (pin "6") (pinfunction "GPIOA1_6") (pintype "bidirectional"))
    )
    (net (code "85") (name "unconnected-(MS2-NC-Pad16)") (class "Default")
      (node (ref "MS2") (pin "16") (pinfunction "NC_16") (pintype "passive"))
    )
  )
)
